# S7CAS-PLEIADES-CARTE-MERE_P20_ADC.net
KiCad netlist of a schematic drawn in Altium Designer
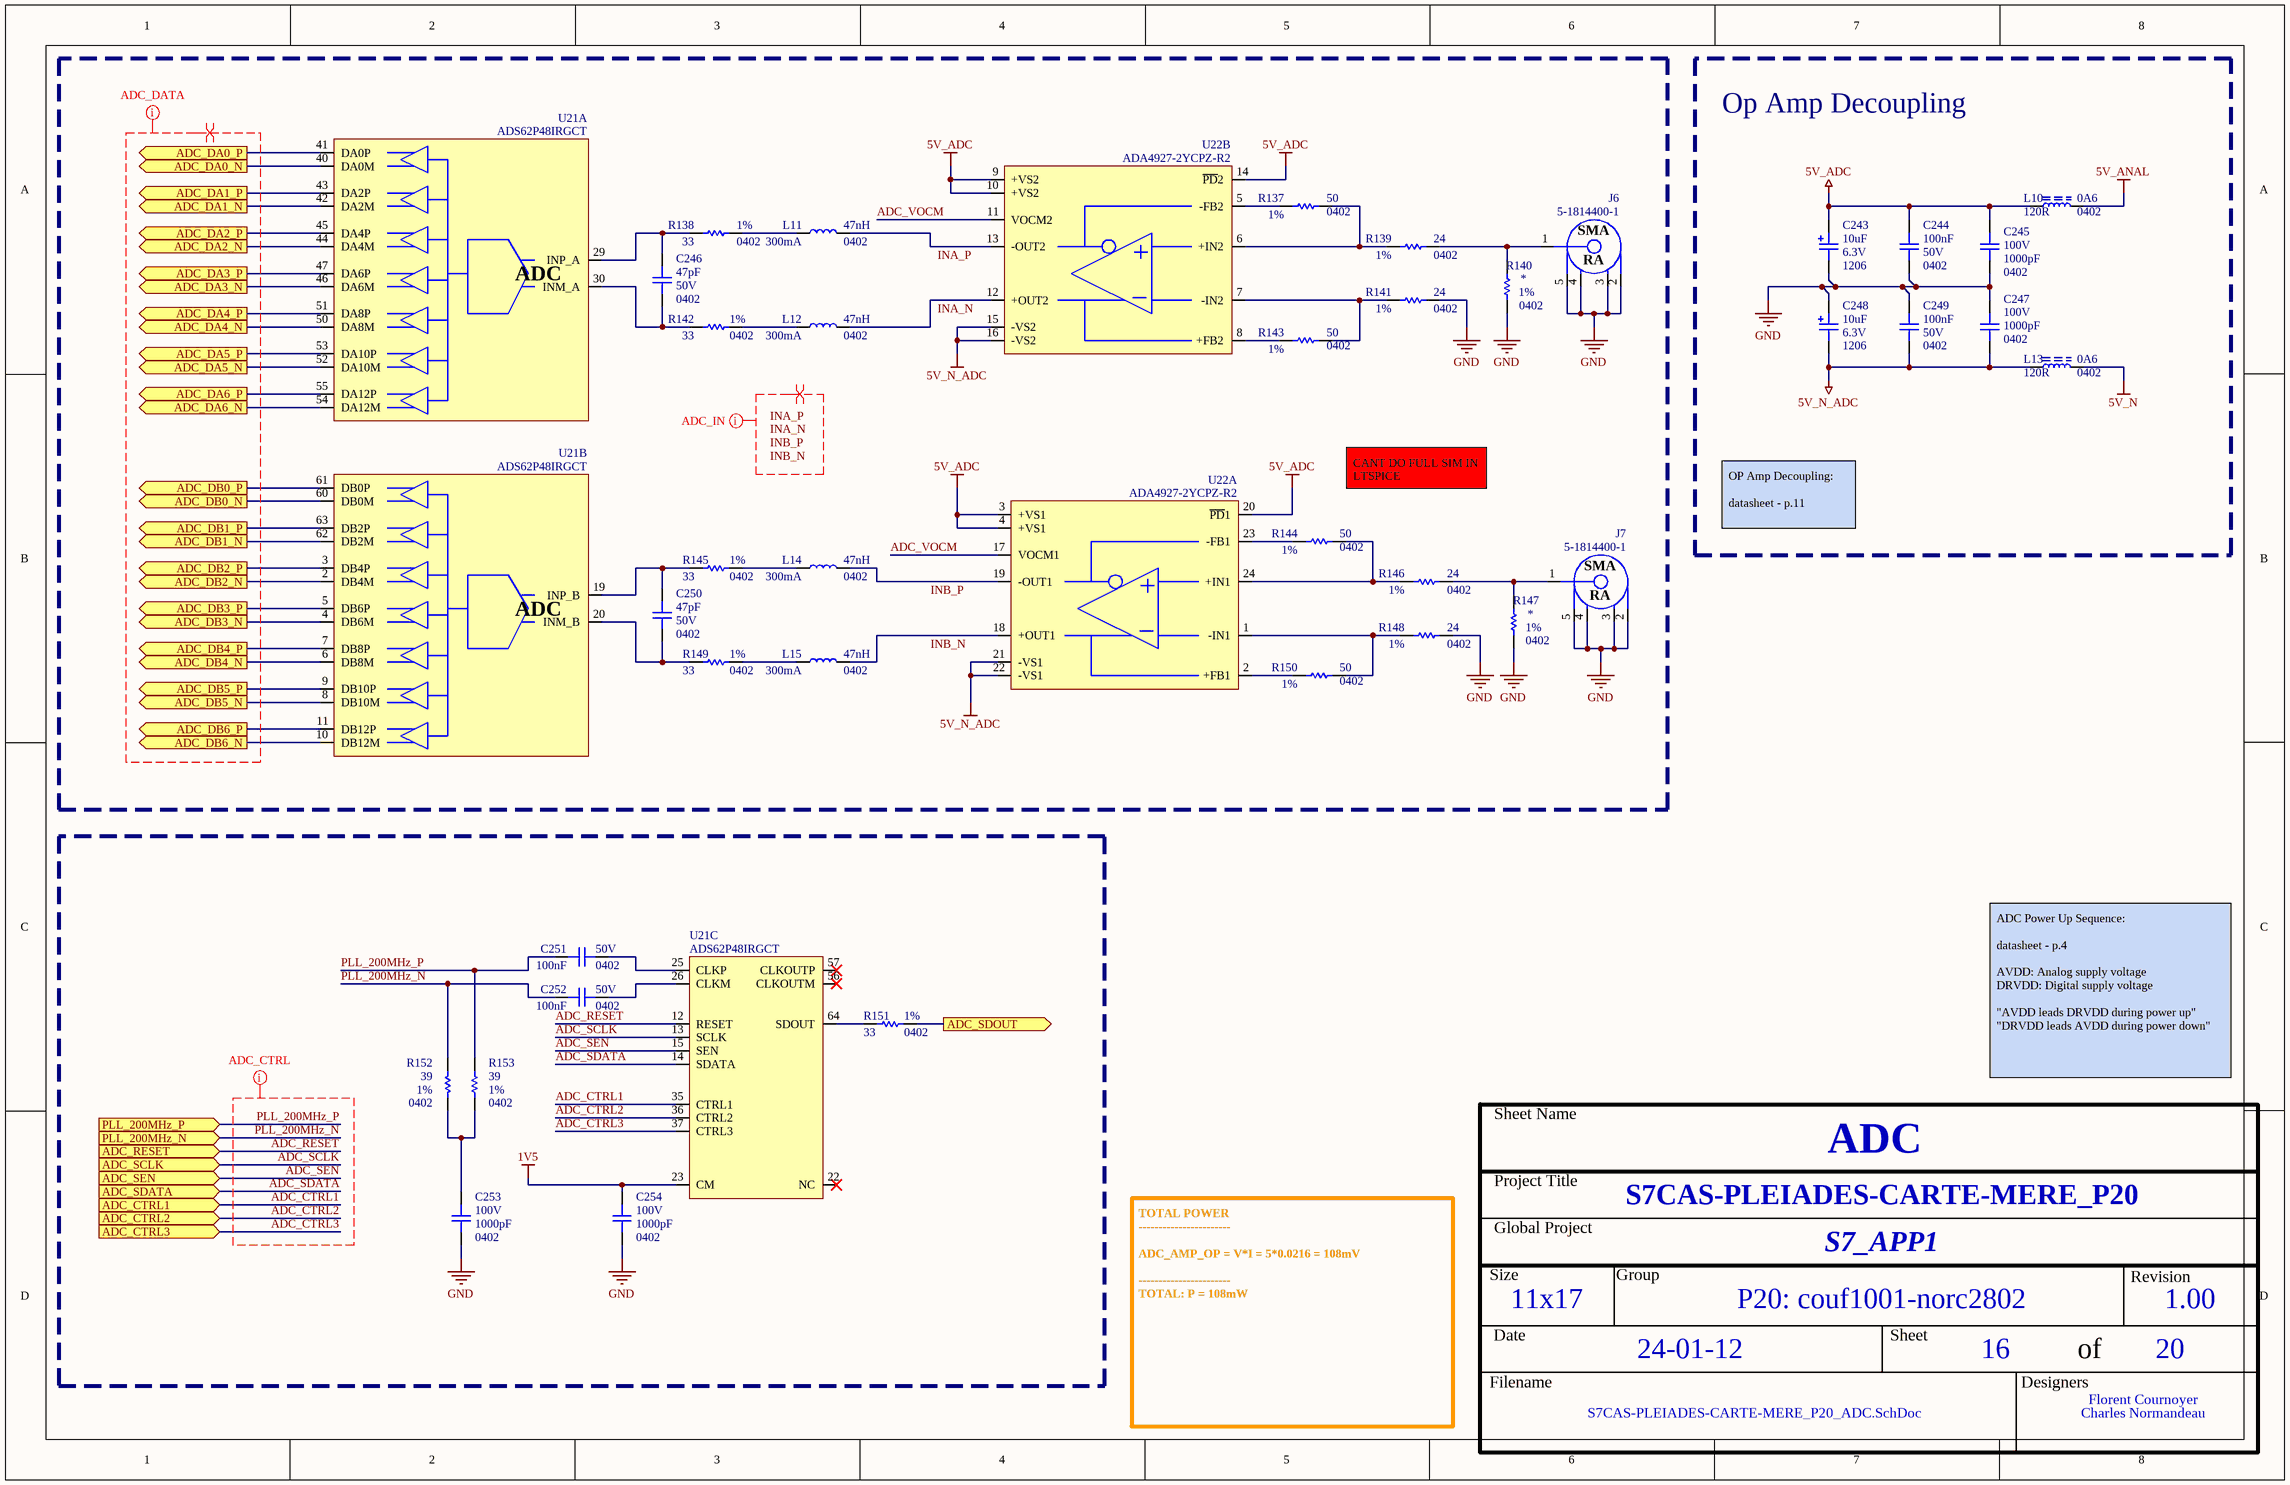
[diagram p0: S7CAS-PLEIADES-CARTE-MERE_P20_ADC.SchDoc]

(export (version "E")
  (design (tool "Eeschema 10.0.6"))
  (components
    (comp (ref "C243")
      (value "10uF")
      (footprint "CAP_TAN_1206(A)")
      (description "CAP - TANTALUM - 1206")
      (fields
        (field (name "MFG PART NUMBER") "TBD")
        (field (name "VOLTAGE") "6.3V")
        (field (name "PACKAGE") "1206")
        (field (name "Comment") "CAP - TANTALUM - CASE A")
        (field (name "CREATEDBY") "Jonathan Bouchard")
      )
      (libsource (lib "S7CAS_LIB2023") (part "CAP_TANT_1206(A)"))
    )
    (comp (ref "C244")
      (value "100nF")
      (footprint "CAP_0402")
      (description "CAP - 0402")
      (fields
        (field (name "MFG PART NUMBER") "GRM155R61H104KE14")
        (field (name "VOLTAGE") "50V")
        (field (name "PACKAGE") "0402")
        (field (name "CREATEDBY") "Jonathan Bouchard")
      )
      (libsource (lib "S7CAS_LIB2023") (part "CAP - 0402"))
    )
    (comp (ref "C245")
      (value "1000pF")
      (footprint "CAP_0402")
      (description "CAP - 0402")
      (fields
        (field (name "MFG PART NUMBER") "GRM155R72A102KA01")
        (field (name "VOLTAGE") "100V")
        (field (name "PACKAGE") "0402")
        (field (name "CREATEDBY") "Jonathan Bouchard")
      )
      (libsource (lib "S7CAS_LIB2023") (part "CAP - 0402"))
    )
    (comp (ref "C246")
      (value "47pF")
      (footprint "CAP_0402")
      (description "CAP - 0402")
      (fields
        (field (name "MFG PART NUMBER") "GRM1555C1H470GA01")
        (field (name "VOLTAGE") "50V")
        (field (name "PACKAGE") "0402")
        (field (name "CREATEDBY") "Jonathan Bouchard")
      )
      (libsource (lib "S7CAS_LIB2023") (part "CAP - 0402"))
    )
    (comp (ref "C247")
      (value "1000pF")
      (footprint "CAP_0402")
      (description "CAP - 0402")
      (fields
        (field (name "MFG PART NUMBER") "GRM155R72A102KA01")
        (field (name "VOLTAGE") "100V")
        (field (name "PACKAGE") "0402")
        (field (name "CREATEDBY") "Jonathan Bouchard")
      )
      (libsource (lib "S7CAS_LIB2023") (part "CAP - 0402"))
    )
    (comp (ref "C248")
      (value "10uF")
      (footprint "CAP_TAN_1206(A)")
      (description "CAP - TANTALUM - 1206")
      (fields
        (field (name "MFG PART NUMBER") "TBD")
        (field (name "VOLTAGE") "6.3V")
        (field (name "PACKAGE") "1206")
        (field (name "Comment") "CAP - TANTALUM - CASE A")
        (field (name "CREATEDBY") "Jonathan Bouchard")
      )
      (libsource (lib "S7CAS_LIB2023") (part "CAP_TANT_1206(A)"))
    )
    (comp (ref "C249")
      (value "100nF")
      (footprint "CAP_0402")
      (description "CAP - 0402")
      (fields
        (field (name "MFG PART NUMBER") "GRM155R61H104KE14")
        (field (name "VOLTAGE") "50V")
        (field (name "PACKAGE") "0402")
        (field (name "CREATEDBY") "Jonathan Bouchard")
      )
      (libsource (lib "S7CAS_LIB2023") (part "CAP - 0402"))
    )
    (comp (ref "C250")
      (value "47pF")
      (footprint "CAP_0402")
      (description "CAP - 0402")
      (fields
        (field (name "MFG PART NUMBER") "GRM1555C1H470GA01")
        (field (name "VOLTAGE") "50V")
        (field (name "PACKAGE") "0402")
        (field (name "CREATEDBY") "Jonathan Bouchard")
      )
      (libsource (lib "S7CAS_LIB2023") (part "CAP - 0402"))
    )
    (comp (ref "C251")
      (value "100nF")
      (footprint "CAP_0402")
      (description "CAP - 0402")
      (fields
        (field (name "MFG PART NUMBER") "GRM155R61H104KE14")
        (field (name "VOLTAGE") "50V")
        (field (name "PACKAGE") "0402")
        (field (name "CREATEDBY") "Jonathan Bouchard")
      )
      (libsource (lib "S7CAS_LIB2023") (part "CAP - 0402"))
    )
    (comp (ref "C252")
      (value "100nF")
      (footprint "CAP_0402")
      (description "CAP - 0402")
      (fields
        (field (name "MFG PART NUMBER") "GRM155R61H104KE14")
        (field (name "VOLTAGE") "50V")
        (field (name "PACKAGE") "0402")
        (field (name "CREATEDBY") "Jonathan Bouchard")
      )
      (libsource (lib "S7CAS_LIB2023") (part "CAP - 0402"))
    )
    (comp (ref "C253")
      (value "1000pF")
      (footprint "CAP_0402")
      (description "CAP - 0402")
      (fields
        (field (name "MFG PART NUMBER") "GRM155R72A102KA01")
        (field (name "VOLTAGE") "100V")
        (field (name "PACKAGE") "0402")
        (field (name "CREATEDBY") "Jonathan Bouchard")
      )
      (libsource (lib "S7CAS_LIB2023") (part "CAP - 0402"))
    )
    (comp (ref "C254")
      (value "1000pF")
      (footprint "CAP_0402")
      (description "CAP - 0402")
      (fields
        (field (name "MFG PART NUMBER") "GRM155R72A102KA01")
        (field (name "VOLTAGE") "100V")
        (field (name "PACKAGE") "0402")
        (field (name "CREATEDBY") "Jonathan Bouchard")
      )
      (libsource (lib "S7CAS_LIB2023") (part "CAP - 0402"))
    )
    (comp (ref "J6")
      (value "5-1814400-1")
      (footprint "CONN_SMA_5-1814400-1")
      (description "CONN -  SMA JACK R/A 50 OHM - TH")
      (fields
        (field (name "MFG") "TE Connectivity AMP Connectors")
        (field (name "CREATEDBY") "Jonathan Bouchard")
      )
      (libsource (lib "S7CAS_LIB2023") (part "CONN_SMA_5-1814400-1"))
    )
    (comp (ref "J7")
      (value "5-1814400-1")
      (footprint "CONN_SMA_5-1814400-1")
      (description "CONN -  SMA JACK R/A 50 OHM - TH")
      (fields
        (field (name "MFG") "TE Connectivity AMP Connectors")
        (field (name "CREATEDBY") "Jonathan Bouchard")
      )
      (libsource (lib "S7CAS_LIB2023") (part "CONN_SMA_5-1814400-1"))
    )
    (comp (ref "L10")
      (value "120R")
      (footprint "FER_0402")
      (description "FER - 0402")
      (fields
        (field (name "MFG PART NUMBER") "BLM15BX121SN1")
        (field (name "CURRENT") "0A6")
        (field (name "PACKAGE") "0402")
        (field (name "CREATEDBY") "Jonathan Bouchard")
      )
      (libsource (lib "S7CAS_LIB2023") (part "FER - 0402"))
    )
    (comp (ref "L11")
      (value "47nH")
      (footprint "IND_0402")
      (description "IND - 0402")
      (fields
        (field (name "MFG PART NUMBER") "TBD")
        (field (name "CURRENT") "300mA")
        (field (name "PACKAGE") "0402")
        (field (name "Comment") "Part Number")
      )
      (libsource (lib "LIB_TEMP_P20_FLORENT_COURNOYER_SCH") (part "IND - 0402"))
    )
    (comp (ref "L12")
      (value "47nH")
      (footprint "IND_0402")
      (description "IND - 0402")
      (fields
        (field (name "MFG PART NUMBER") "TBD")
        (field (name "CURRENT") "300mA")
        (field (name "PACKAGE") "0402")
        (field (name "Comment") "Part Number")
      )
      (libsource (lib "LIB_TEMP_P20_FLORENT_COURNOYER_SCH") (part "IND - 0402"))
    )
    (comp (ref "L13")
      (value "120R")
      (footprint "FER_0402")
      (description "FER - 0402")
      (fields
        (field (name "MFG PART NUMBER") "BLM15BX121SN1")
        (field (name "CURRENT") "0A6")
        (field (name "PACKAGE") "0402")
        (field (name "CREATEDBY") "Jonathan Bouchard")
      )
      (libsource (lib "S7CAS_LIB2023") (part "FER - 0402"))
    )
    (comp (ref "L14")
      (value "47nH")
      (footprint "IND_0402")
      (description "IND - 0402")
      (fields
        (field (name "MFG PART NUMBER") "TBD")
        (field (name "CURRENT") "300mA")
        (field (name "PACKAGE") "0402")
        (field (name "Comment") "Part Number")
      )
      (libsource (lib "LIB_TEMP_P20_FLORENT_COURNOYER_SCH") (part "IND - 0402"))
    )
    (comp (ref "L15")
      (value "47nH")
      (footprint "IND_0402")
      (description "IND - 0402")
      (fields
        (field (name "MFG PART NUMBER") "TBD")
        (field (name "CURRENT") "300mA")
        (field (name "PACKAGE") "0402")
        (field (name "Comment") "Part Number")
      )
      (libsource (lib "LIB_TEMP_P20_FLORENT_COURNOYER_SCH") (part "IND - 0402"))
    )
    (comp (ref "R137")
      (value "50")
      (footprint "RES_0402")
      (description "RES - 0402")
      (fields
        (field (name "VOLTAGE") "50V")
        (field (name "MFG PART NUMBER") "FC0402E50R0FTBST0")
        (field (name "PACKAGE") "0402")
        (field (name "PRECISION") "1%")
        (field (name "CREATEDBY") "Jonathan Bouchard")
      )
      (libsource (lib "S7CAS_LIB2023") (part "RES - 0402"))
    )
    (comp (ref "R138")
      (value "33")
      (footprint "RES_0402")
      (description "RES - 0402")
      (fields
        (field (name "VOLTAGE") "50V")
        (field (name "MFG PART NUMBER") "CRCW040233R0FKEDC")
        (field (name "PACKAGE") "0402")
        (field (name "PRECISION") "1%")
        (field (name "CREATEDBY") "Jonathan Bouchard")
      )
      (libsource (lib "S7CAS_LIB2023") (part "RES - 0402"))
    )
    (comp (ref "R139")
      (value "24")
      (footprint "RES_0402")
      (description "RES - 0402")
      (fields
        (field (name "VOLTAGE") "50V")
        (field (name "MFG PART NUMBER") "MCS04020C2409FE000")
        (field (name "PACKAGE") "0402")
        (field (name "PRECISION") "1%")
        (field (name "CREATEDBY") "Jonathan Bouchard")
      )
      (libsource (lib "S7CAS_LIB2023") (part "RES - 0402"))
    )
    (comp (ref "R140")
      (value "RES - 0402")
      (footprint "RES_0402")
      (fields
        (field (name "VOLTAGE") "50V")
        (field (name "POWER") "1/16W")
        (field (name "PACKAGE") "0402")
        (field (name "PRECISION") "1%")
        (field (name "ALTIUM_VALUE") "*")
        (field (name "CREATEDBY") "Jonathan Bouchard")
      )
      (libsource (lib "S7CAS_LIB2023") (part "RES - 0402"))
    )
    (comp (ref "R141")
      (value "24")
      (footprint "RES_0402")
      (description "RES - 0402")
      (fields
        (field (name "VOLTAGE") "50V")
        (field (name "MFG PART NUMBER") "MCS04020C2409FE000")
        (field (name "PACKAGE") "0402")
        (field (name "PRECISION") "1%")
        (field (name "CREATEDBY") "Jonathan Bouchard")
      )
      (libsource (lib "S7CAS_LIB2023") (part "RES - 0402"))
    )
    (comp (ref "R142")
      (value "33")
      (footprint "RES_0402")
      (description "RES - 0402")
      (fields
        (field (name "VOLTAGE") "50V")
        (field (name "MFG PART NUMBER") "CRCW040233R0FKEDC")
        (field (name "PACKAGE") "0402")
        (field (name "PRECISION") "1%")
        (field (name "CREATEDBY") "Jonathan Bouchard")
      )
      (libsource (lib "S7CAS_LIB2023") (part "RES - 0402"))
    )
    (comp (ref "R143")
      (value "50")
      (footprint "RES_0402")
      (description "RES - 0402")
      (fields
        (field (name "VOLTAGE") "50V")
        (field (name "MFG PART NUMBER") "FC0402E50R0FTBST0")
        (field (name "PACKAGE") "0402")
        (field (name "PRECISION") "1%")
        (field (name "CREATEDBY") "Jonathan Bouchard")
      )
      (libsource (lib "S7CAS_LIB2023") (part "RES - 0402"))
    )
    (comp (ref "R144")
      (value "50")
      (footprint "RES_0402")
      (description "RES - 0402")
      (fields
        (field (name "VOLTAGE") "50V")
        (field (name "MFG PART NUMBER") "FC0402E50R0FTBST0")
        (field (name "PACKAGE") "0402")
        (field (name "PRECISION") "1%")
        (field (name "CREATEDBY") "Jonathan Bouchard")
      )
      (libsource (lib "S7CAS_LIB2023") (part "RES - 0402"))
    )
    (comp (ref "R145")
      (value "33")
      (footprint "RES_0402")
      (description "RES - 0402")
      (fields
        (field (name "VOLTAGE") "50V")
        (field (name "MFG PART NUMBER") "CRCW040233R0FKEDC")
        (field (name "PACKAGE") "0402")
        (field (name "PRECISION") "1%")
        (field (name "CREATEDBY") "Jonathan Bouchard")
      )
      (libsource (lib "S7CAS_LIB2023") (part "RES - 0402"))
    )
    (comp (ref "R146")
      (value "24")
      (footprint "RES_0402")
      (description "RES - 0402")
      (fields
        (field (name "VOLTAGE") "50V")
        (field (name "MFG PART NUMBER") "MCS04020C2409FE000")
        (field (name "PACKAGE") "0402")
        (field (name "PRECISION") "1%")
        (field (name "CREATEDBY") "Jonathan Bouchard")
      )
      (libsource (lib "S7CAS_LIB2023") (part "RES - 0402"))
    )
    (comp (ref "R147")
      (value "RES - 0402")
      (footprint "RES_0402")
      (fields
        (field (name "VOLTAGE") "50V")
        (field (name "POWER") "1/16W")
        (field (name "PACKAGE") "0402")
        (field (name "PRECISION") "1%")
        (field (name "ALTIUM_VALUE") "*")
        (field (name "CREATEDBY") "Jonathan Bouchard")
      )
      (libsource (lib "S7CAS_LIB2023") (part "RES - 0402"))
    )
    (comp (ref "R148")
      (value "24")
      (footprint "RES_0402")
      (description "RES - 0402")
      (fields
        (field (name "VOLTAGE") "50V")
        (field (name "MFG PART NUMBER") "MCS04020C2409FE000")
        (field (name "PACKAGE") "0402")
        (field (name "PRECISION") "1%")
        (field (name "CREATEDBY") "Jonathan Bouchard")
      )
      (libsource (lib "S7CAS_LIB2023") (part "RES - 0402"))
    )
    (comp (ref "R149")
      (value "33")
      (footprint "RES_0402")
      (description "RES - 0402")
      (fields
        (field (name "VOLTAGE") "50V")
        (field (name "MFG PART NUMBER") "CRCW040233R0FKEDC")
        (field (name "PACKAGE") "0402")
        (field (name "PRECISION") "1%")
        (field (name "CREATEDBY") "Jonathan Bouchard")
      )
      (libsource (lib "S7CAS_LIB2023") (part "RES - 0402"))
    )
    (comp (ref "R150")
      (value "50")
      (footprint "RES_0402")
      (description "RES - 0402")
      (fields
        (field (name "VOLTAGE") "50V")
        (field (name "MFG PART NUMBER") "FC0402E50R0FTBST0")
        (field (name "PACKAGE") "0402")
        (field (name "PRECISION") "1%")
        (field (name "CREATEDBY") "Jonathan Bouchard")
      )
      (libsource (lib "S7CAS_LIB2023") (part "RES - 0402"))
    )
    (comp (ref "R151")
      (value "33")
      (footprint "RES_0402")
      (description "RES - 0402")
      (fields
        (field (name "VOLTAGE") "50V")
        (field (name "MFG PART NUMBER") "CRCW040233R0FKEDC")
        (field (name "PACKAGE") "0402")
        (field (name "PRECISION") "1%")
        (field (name "CREATEDBY") "Jonathan Bouchard")
      )
      (libsource (lib "S7CAS_LIB2023") (part "RES - 0402"))
    )
    (comp (ref "R152")
      (value "39")
      (footprint "RES_0402")
      (description "RES - 0402")
      (fields
        (field (name "VOLTAGE") "50")
        (field (name "MFG PART NUMBER") "RL0510S-390-F")
        (field (name "PACKAGE") "0402")
        (field (name "PRECISION") "1%")
        (field (name "CREATEDBY") "Jonathan Bouchard")
      )
      (libsource (lib "S7CAS_LIB2023") (part "RES - 0402"))
    )
    (comp (ref "R153")
      (value "39")
      (footprint "RES_0402")
      (description "RES - 0402")
      (fields
        (field (name "VOLTAGE") "50")
        (field (name "MFG PART NUMBER") "RL0510S-390-F")
        (field (name "PACKAGE") "0402")
        (field (name "PRECISION") "1%")
        (field (name "CREATEDBY") "Jonathan Bouchard")
      )
      (libsource (lib "S7CAS_LIB2023") (part "RES - 0402"))
    )
    (comp (ref "U21")
      (value "ADS62P48IRGCT")
      (footprint "ADC_ADS62P48IRGCT")
      (description "ADC - 14 BIT 210MSPS SUAL - VQFN-64")
      (fields
        (field (name "VOLTAGE") "3.15 V ~ 3.6 V / 1.7 V ~ 1.9 V")
        (field (name "MFG") "Texas Instruments")
        (field (name "CREATEDBY") "Jonathan Bouchard")
      )
      (libsource (lib "S7CAS_LIB2023") (part "ADC_ADS62P48IRGCT"))
    )
    (comp (ref "U22")
      (value "ADA4927-2YCPZ-R2")
      (footprint "OPAMP_ADA4927-2YCPZ-R2")
      (description "OPAMP - CFA 2.3GHZ - QFN-24")
      (fields
        (field (name "VOLTAGE") "4.5 V ~ 11 V, ±2.25 V ~ 5.5 V")
        (field (name "MFG") "Analog Devices")
        (field (name "CREATEDBY") "Jonathan Bouchard")
      )
      (libsource (lib "S7CAS_LIB2023") (part "OPAMP_ADA4927-2YCPZ-R2"))
    )
  )
  (nets
    (net (code "1") (name "/ADC_CTRL1") (class "Default")
      (node (ref "U21") (pin "35") (pinfunction "CTRL1_35") (pintype "passive"))
    )
    (net (code "2") (name "/ADC_CTRL2") (class "Default")
      (node (ref "U21") (pin "36") (pinfunction "CTRL2_36") (pintype "passive"))
    )
    (net (code "3") (name "/ADC_CTRL3") (class "Default")
      (node (ref "U21") (pin "37") (pinfunction "CTRL3_37") (pintype "passive"))
    )
    (net (code "4") (name "/ADC_DA0_N") (class "Default")
      (node (ref "U21") (pin "40") (pinfunction "DA0M_40") (pintype "passive"))
    )
    (net (code "5") (name "/ADC_DA0_P") (class "Default")
      (node (ref "U21") (pin "41") (pinfunction "DA0P_41") (pintype "passive"))
    )
    (net (code "6") (name "/ADC_DA1_N") (class "Default")
      (node (ref "U21") (pin "42") (pinfunction "DA2M_42") (pintype "passive"))
    )
    (net (code "7") (name "/ADC_DA1_P") (class "Default")
      (node (ref "U21") (pin "43") (pinfunction "DA2P_43") (pintype "passive"))
    )
    (net (code "8") (name "/ADC_DA2_N") (class "Default")
      (node (ref "U21") (pin "44") (pinfunction "DA4M_44") (pintype "passive"))
    )
    (net (code "9") (name "/ADC_DA2_P") (class "Default")
      (node (ref "U21") (pin "45") (pinfunction "DA4P_45") (pintype "passive"))
    )
    (net (code "10") (name "/ADC_DA3_N") (class "Default")
      (node (ref "U21") (pin "46") (pinfunction "DA6M_46") (pintype "passive"))
    )
    (net (code "11") (name "/ADC_DA3_P") (class "Default")
      (node (ref "U21") (pin "47") (pinfunction "DA6P_47") (pintype "passive"))
    )
    (net (code "12") (name "/ADC_DA4_N") (class "Default")
      (node (ref "U21") (pin "50") (pinfunction "DA8M_50") (pintype "passive"))
    )
    (net (code "13") (name "/ADC_DA4_P") (class "Default")
      (node (ref "U21") (pin "51") (pinfunction "DA8P_51") (pintype "passive"))
    )
    (net (code "14") (name "/ADC_DA5_N") (class "Default")
      (node (ref "U21") (pin "52") (pinfunction "DA10M_52") (pintype "passive"))
    )
    (net (code "15") (name "/ADC_DA5_P") (class "Default")
      (node (ref "U21") (pin "53") (pinfunction "DA10P_53") (pintype "passive"))
    )
    (net (code "16") (name "/ADC_DA6_N") (class "Default")
      (node (ref "U21") (pin "54") (pinfunction "DA12M_54") (pintype "passive"))
    )
    (net (code "17") (name "/ADC_DA6_P") (class "Default")
      (node (ref "U21") (pin "55") (pinfunction "DA12P_55") (pintype "passive"))
    )
    (net (code "18") (name "/ADC_DB0_N") (class "Default")
      (node (ref "U21") (pin "60") (pinfunction "DB0M_60") (pintype "passive"))
    )
    (net (code "19") (name "/ADC_DB0_P") (class "Default")
      (node (ref "U21") (pin "61") (pinfunction "DB0P_61") (pintype "passive"))
    )
    (net (code "20") (name "/ADC_DB1_N") (class "Default")
      (node (ref "U21") (pin "62") (pinfunction "DB2M_62") (pintype "passive"))
    )
    (net (code "21") (name "/ADC_DB1_P") (class "Default")
      (node (ref "U21") (pin "63") (pinfunction "DB2P_63") (pintype "passive"))
    )
    (net (code "22") (name "/ADC_DB2_N") (class "Default")
      (node (ref "U21") (pin "2") (pinfunction "DB4M_2") (pintype "passive"))
    )
    (net (code "23") (name "/ADC_DB2_P") (class "Default")
      (node (ref "U21") (pin "3") (pinfunction "DB4P_3") (pintype "passive"))
    )
    (net (code "24") (name "/ADC_DB3_N") (class "Default")
      (node (ref "U21") (pin "4") (pinfunction "DB6M_4") (pintype "passive"))
    )
    (net (code "25") (name "/ADC_DB3_P") (class "Default")
      (node (ref "U21") (pin "5") (pinfunction "DB6P_5") (pintype "passive"))
    )
    (net (code "26") (name "/ADC_DB4_N") (class "Default")
      (node (ref "U21") (pin "6") (pinfunction "DB8M_6") (pintype "passive"))
    )
    (net (code "27") (name "/ADC_DB4_P") (class "Default")
      (node (ref "U21") (pin "7") (pinfunction "DB8P_7") (pintype "passive"))
    )
    (net (code "28") (name "/ADC_DB5_N") (class "Default")
      (node (ref "U21") (pin "8") (pinfunction "DB10M_8") (pintype "passive"))
    )
    (net (code "29") (name "/ADC_DB5_P") (class "Default")
      (node (ref "U21") (pin "9") (pinfunction "DB10P_9") (pintype "passive"))
    )
    (net (code "30") (name "/ADC_DB6_N") (class "Default")
      (node (ref "U21") (pin "10") (pinfunction "DB12M_10") (pintype "passive"))
    )
    (net (code "31") (name "/ADC_DB6_P") (class "Default")
      (node (ref "U21") (pin "11") (pinfunction "DB12P_11") (pintype "passive"))
    )
    (net (code "32") (name "/ADC_RESET") (class "Default")
      (node (ref "U21") (pin "12") (pinfunction "RESET_12") (pintype "passive"))
    )
    (net (code "33") (name "/ADC_SCLK") (class "Default")
      (node (ref "U21") (pin "13") (pinfunction "SCLK_13") (pintype "passive"))
    )
    (net (code "34") (name "/ADC_SDATA") (class "Default")
      (node (ref "U21") (pin "14") (pinfunction "SDATA_14") (pintype "passive"))
    )
    (net (code "35") (name "/ADC_SDOUT") (class "Default")
      (node (ref "R151") (pin "1") (pinfunction "1_1") (pintype "passive"))
    )
    (net (code "36") (name "/ADC_SEN") (class "Default")
      (node (ref "U21") (pin "15") (pinfunction "SEN_15") (pintype "passive"))
    )
    (net (code "37") (name "/ADC_VOCM") (class "Default")
      (node (ref "U22") (pin "11") (pinfunction "VOCM2_11") (pintype "passive"))
      (node (ref "U22") (pin "17") (pinfunction "VOCM1_17") (pintype "passive"))
    )
    (net (code "38") (name "/INA_N") (class "Default")
      (node (ref "L12") (pin "2") (pinfunction "2_2") (pintype "passive"))
      (node (ref "U22") (pin "12") (pinfunction "+OUT2_12") (pintype "passive"))
    )
    (net (code "39") (name "/INA_P") (class "Default")
      (node (ref "L11") (pin "2") (pinfunction "2_2") (pintype "passive"))
      (node (ref "U22") (pin "13") (pinfunction "-OUT2_13") (pintype "passive"))
    )
    (net (code "40") (name "/INB_N") (class "Default")
      (node (ref "L15") (pin "2") (pinfunction "2_2") (pintype "passive"))
      (node (ref "U22") (pin "18") (pinfunction "+OUT1_18") (pintype "passive"))
    )
    (net (code "41") (name "/INB_P") (class "Default")
      (node (ref "L14") (pin "2") (pinfunction "2_2") (pintype "passive"))
      (node (ref "U22") (pin "19") (pinfunction "-OUT1_19") (pintype "passive"))
    )
    (net (code "42") (name "/PLL_200MHz_N") (class "Default")
      (node (ref "C252") (pin "2") (pinfunction "2_2") (pintype "passive"))
      (node (ref "R152") (pin "2") (pinfunction "2_2") (pintype "passive"))
    )
    (net (code "43") (name "/PLL_200MHz_P") (class "Default")
      (node (ref "C251") (pin "2") (pinfunction "2_2") (pintype "passive"))
      (node (ref "R153") (pin "2") (pinfunction "2_2") (pintype "passive"))
    )
    (net (code "44") (name "1V5") (class "Default")
      (node (ref "C254") (pin "1") (pinfunction "1_1") (pintype "passive"))
      (node (ref "U21") (pin "23") (pinfunction "CM_23") (pintype "passive"))
    )
    (net (code "45") (name "5V_ADC") (class "Default")
      (node (ref "C243") (pin "2") (pinfunction "2_2") (pintype "passive"))
      (node (ref "C244") (pin "2") (pinfunction "2_2") (pintype "passive"))
      (node (ref "C245") (pin "1") (pinfunction "1_1") (pintype "passive"))
      (node (ref "L10") (pin "2") (pinfunction "2_2") (pintype "passive"))
      (node (ref "U22") (pin "10") (pinfunction "+VS2_10") (pintype "passive"))
      (node (ref "U22") (pin "14") (pinfunction "~{PD}2_14") (pintype "passive"))
      (node (ref "U22") (pin "20") (pinfunction "~{PD}1_20") (pintype "passive"))
      (node (ref "U22") (pin "3") (pinfunction "+VS1_3") (pintype "passive"))
      (node (ref "U22") (pin "4") (pinfunction "+VS1_4") (pintype "passive"))
      (node (ref "U22") (pin "9") (pinfunction "+VS2_9") (pintype "passive"))
    )
    (net (code "46") (name "5V_ANAL") (class "Default")
      (node (ref "L10") (pin "1") (pinfunction "1_1") (pintype "passive"))
    )
    (net (code "47") (name "5V_N") (class "Default")
      (node (ref "L13") (pin "1") (pinfunction "1_1") (pintype "passive"))
    )
    (net (code "48") (name "5V_N_ADC") (class "Default")
      (node (ref "C247") (pin "2") (pinfunction "2_2") (pintype "passive"))
      (node (ref "C248") (pin "1") (pinfunction "1_1") (pintype "passive"))
      (node (ref "C249") (pin "1") (pinfunction "1_1") (pintype "passive"))
      (node (ref "L13") (pin "2") (pinfunction "2_2") (pintype "passive"))
      (node (ref "U22") (pin "15") (pinfunction "-VS2_15") (pintype "passive"))
      (node (ref "U22") (pin "16") (pinfunction "-VS2_16") (pintype "passive"))
      (node (ref "U22") (pin "21") (pinfunction "-VS1_21") (pintype "passive"))
      (node (ref "U22") (pin "22") (pinfunction "-VS1_22") (pintype "passive"))
    )
    (net (code "49") (name "GND") (class "Default")
      (node (ref "C243") (pin "1") (pinfunction "1_1") (pintype "passive"))
      (node (ref "C244") (pin "1") (pinfunction "1_1") (pintype "passive"))
      (node (ref "C245") (pin "2") (pinfunction "2_2") (pintype "passive"))
      (node (ref "C247") (pin "1") (pinfunction "1_1") (pintype "passive"))
      (node (ref "C248") (pin "2") (pinfunction "2_2") (pintype "passive"))
      (node (ref "C249") (pin "2") (pinfunction "2_2") (pintype "passive"))
      (node (ref "C253") (pin "2") (pinfunction "2_2") (pintype "passive"))
      (node (ref "C254") (pin "2") (pinfunction "2_2") (pintype "passive"))
      (node (ref "J6") (pin "2") (pinfunction "2_2") (pintype "passive"))
      (node (ref "J6") (pin "3") (pinfunction "3_3") (pintype "passive"))
      (node (ref "J6") (pin "4") (pinfunction "4_4") (pintype "passive"))
      (node (ref "J6") (pin "5") (pinfunction "5_5") (pintype "passive"))
      (node (ref "J7") (pin "2") (pinfunction "2_2") (pintype "passive"))
      (node (ref "J7") (pin "3") (pinfunction "3_3") (pintype "passive"))
      (node (ref "J7") (pin "4") (pinfunction "4_4") (pintype "passive"))
      (node (ref "J7") (pin "5") (pinfunction "5_5") (pintype "passive"))
      (node (ref "R140") (pin "1") (pinfunction "1_1") (pintype "passive"))
      (node (ref "R141") (pin "1") (pinfunction "1_1") (pintype "passive"))
      (node (ref "R147") (pin "1") (pinfunction "1_1") (pintype "passive"))
      (node (ref "R148") (pin "1") (pinfunction "1_1") (pintype "passive"))
    )
    (net (code "50") (name "Net-(C253-Pad1)") (class "Default")
      (node (ref "C253") (pin "1") (pinfunction "1_1") (pintype "passive"))
      (node (ref "R152") (pin "1") (pinfunction "1_1") (pintype "passive"))
      (node (ref "R153") (pin "1") (pinfunction "1_1") (pintype "passive"))
    )
    (net (code "51") (name "Net-(J6-Pad1)") (class "Default")
      (node (ref "J6") (pin "1") (pinfunction "1_1") (pintype "passive"))
      (node (ref "R139") (pin "1") (pinfunction "1_1") (pintype "passive"))
      (node (ref "R140") (pin "2") (pinfunction "2_2") (pintype "passive"))
    )
    (net (code "52") (name "Net-(J7-Pad1)") (class "Default")
      (node (ref "J7") (pin "1") (pinfunction "1_1") (pintype "passive"))
      (node (ref "R146") (pin "1") (pinfunction "1_1") (pintype "passive"))
      (node (ref "R147") (pin "2") (pinfunction "2_2") (pintype "passive"))
    )
    (net (code "53") (name "Net-(L11-Pad1)") (class "Default")
      (node (ref "L11") (pin "1") (pinfunction "1_1") (pintype "passive"))
      (node (ref "R138") (pin "1") (pinfunction "1_1") (pintype "passive"))
    )
    (net (code "54") (name "Net-(L12-Pad1)") (class "Default")
      (node (ref "L12") (pin "1") (pinfunction "1_1") (pintype "passive"))
      (node (ref "R142") (pin "1") (pinfunction "1_1") (pintype "passive"))
    )
    (net (code "55") (name "Net-(L14-Pad1)") (class "Default")
      (node (ref "L14") (pin "1") (pinfunction "1_1") (pintype "passive"))
      (node (ref "R145") (pin "1") (pinfunction "1_1") (pintype "passive"))
    )
    (net (code "56") (name "Net-(L15-Pad1)") (class "Default")
      (node (ref "L15") (pin "1") (pinfunction "1_1") (pintype "passive"))
      (node (ref "R149") (pin "1") (pinfunction "1_1") (pintype "passive"))
    )
    (net (code "57") (name "Net-(U21A-INM_A)") (class "Default")
      (node (ref "C246") (pin "1") (pinfunction "1_1") (pintype "passive"))
      (node (ref "R142") (pin "2") (pinfunction "2_2") (pintype "passive"))
      (node (ref "U21") (pin "30") (pinfunction "INM_A_30") (pintype "passive"))
    )
    (net (code "58") (name "Net-(U21A-INP_A)") (class "Default")
      (node (ref "C246") (pin "2") (pinfunction "2_2") (pintype "passive"))
      (node (ref "R138") (pin "2") (pinfunction "2_2") (pintype "passive"))
      (node (ref "U21") (pin "29") (pinfunction "INP_A_29") (pintype "passive"))
    )
    (net (code "59") (name "Net-(U21B-INM_B)") (class "Default")
      (node (ref "C250") (pin "1") (pinfunction "1_1") (pintype "passive"))
      (node (ref "R149") (pin "2") (pinfunction "2_2") (pintype "passive"))
      (node (ref "U21") (pin "20") (pinfunction "INM_B_20") (pintype "passive"))
    )
    (net (code "60") (name "Net-(U21B-INP_B)") (class "Default")
      (node (ref "C250") (pin "2") (pinfunction "2_2") (pintype "passive"))
      (node (ref "R145") (pin "2") (pinfunction "2_2") (pintype "passive"))
      (node (ref "U21") (pin "19") (pinfunction "INP_B_19") (pintype "passive"))
    )
    (net (code "61") (name "Net-(U21C-CLKM)") (class "Default")
      (node (ref "C252") (pin "1") (pinfunction "1_1") (pintype "passive"))
      (node (ref "U21") (pin "26") (pinfunction "CLKM_26") (pintype "passive"))
    )
    (net (code "62") (name "Net-(U21C-CLKP)") (class "Default")
      (node (ref "C251") (pin "1") (pinfunction "1_1") (pintype "passive"))
      (node (ref "U21") (pin "25") (pinfunction "CLKP_25") (pintype "passive"))
    )
    (net (code "63") (name "Net-(U21C-SDOUT)") (class "Default")
      (node (ref "R151") (pin "2") (pinfunction "2_2") (pintype "passive"))
      (node (ref "U21") (pin "64") (pinfunction "SDOUT_64") (pintype "passive"))
    )
    (net (code "64") (name "Net-(U22A-+FB1)") (class "Default")
      (node (ref "R150") (pin "2") (pinfunction "2_2") (pintype "passive"))
      (node (ref "U22") (pin "2") (pinfunction "+FB1_2") (pintype "passive"))
    )
    (net (code "65") (name "Net-(U22A-+IN1)") (class "Default")
      (node (ref "R144") (pin "1") (pinfunction "1_1") (pintype "passive"))
      (node (ref "R146") (pin "2") (pinfunction "2_2") (pintype "passive"))
      (node (ref "U22") (pin "24") (pinfunction "+IN1_24") (pintype "passive"))
    )
    (net (code "66") (name "Net-(U22A--FB1)") (class "Default")
      (node (ref "R144") (pin "2") (pinfunction "2_2") (pintype "passive"))
      (node (ref "U22") (pin "23") (pinfunction "-FB1_23") (pintype "passive"))
    )
    (net (code "67") (name "Net-(U22A--IN1)") (class "Default")
      (node (ref "R148") (pin "2") (pinfunction "2_2") (pintype "passive"))
      (node (ref "R150") (pin "1") (pinfunction "1_1") (pintype "passive"))
      (node (ref "U22") (pin "1") (pinfunction "-IN1_1") (pintype "passive"))
    )
    (net (code "68") (name "Net-(U22B-+FB2)") (class "Default")
      (node (ref "R143") (pin "2") (pinfunction "2_2") (pintype "passive"))
      (node (ref "U22") (pin "8") (pinfunction "+FB2_8") (pintype "passive"))
    )
    (net (code "69") (name "Net-(U22B-+IN2)") (class "Default")
      (node (ref "R137") (pin "1") (pinfunction "1_1") (pintype "passive"))
      (node (ref "R139") (pin "2") (pinfunction "2_2") (pintype "passive"))
      (node (ref "U22") (pin "6") (pinfunction "+IN2_6") (pintype "passive"))
    )
    (net (code "70") (name "Net-(U22B--FB2)") (class "Default")
      (node (ref "R137") (pin "2") (pinfunction "2_2") (pintype "passive"))
      (node (ref "U22") (pin "5") (pinfunction "-FB2_5") (pintype "passive"))
    )
    (net (code "71") (name "Net-(U22B--IN2)") (class "Default")
      (node (ref "R141") (pin "2") (pinfunction "2_2") (pintype "passive"))
      (node (ref "R143") (pin "1") (pinfunction "1_1") (pintype "passive"))
      (node (ref "U22") (pin "7") (pinfunction "-IN2_7") (pintype "passive"))
    )
    (net (code "72") (name "unconnected-(U21C-CLKOUTM-Pad56)") (class "Default")
      (node (ref "U21") (pin "56") (pinfunction "CLKOUTM_56") (pintype "passive+no_connect"))
    )
    (net (code "73") (name "unconnected-(U21C-CLKOUTP-Pad57)") (class "Default")
      (node (ref "U21") (pin "57") (pinfunction "CLKOUTP_57") (pintype "passive+no_connect"))
    )
    (net (code "74") (name "unconnected-(U21C-NC-Pad22)") (class "Default")
      (node (ref "U21") (pin "22") (pinfunction "NC_22") (pintype "passive+no_connect"))
    )
  )
)
